# I2C_EEPROM_AT24C32.net
KiCad netlist of a schematic drawn in Altium Designer
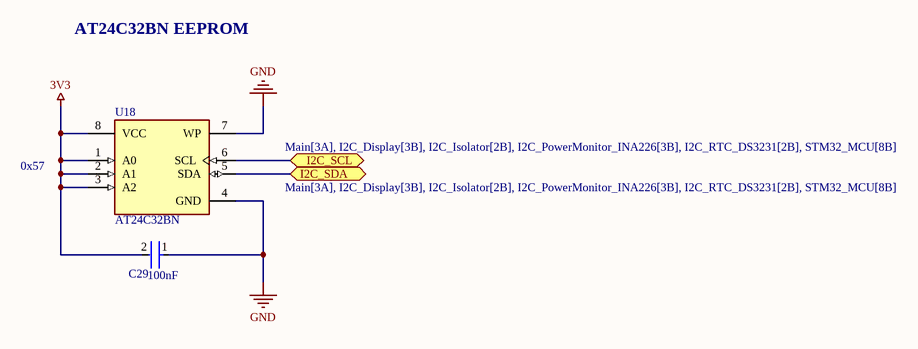
[diagram p0: I2C_EEPROM_AT24C32.SchDoc]

(export (version "E")
  (design (tool "Eeschema 10.0.6"))
  (components
    (comp (ref "C29")
      (value "100nF")
      (footprint "FP-CGA3E-0_3-0_1-IPC_A")
      (description "Cap Ceramic 100nF 50V X7R 10% Pad SMD 0603 +125°C Automotive T/R")
      (fields (field (name "TOLERANCE") "10%") (field (name "VOLTAGE") "50V"))
      (libsource (lib "Altium Content Vault") (part "b4654b650e69147ec39a6b967a45e02"))
    )
    (comp (ref "U18")
      (value "AT24C32BN")
      (footprint "FP-C04-057-SN-MFG")
      (description "IC EEPROM 32KBIT I2C 1MHZ 8SOIC")
      (libsource (lib "Altium Content Vault") (part "960d20628f40e82aadef76fa2b2e794"))
    )
  )
  (nets
    (net (code "1") (name "/I2C_SCL") (class "Default")
      (node (ref "U18") (pin "6") (pinfunction "SCL_6") (pintype "input"))
    )
    (net (code "2") (name "/I2C_SDA") (class "Default")
      (node (ref "U18") (pin "5") (pinfunction "SDA_5") (pintype "bidirectional"))
    )
    (net (code "3") (name "3V3") (class "Default")
      (node (ref "C29") (pin "2") (pinfunction "2_2") (pintype "passive"))
      (node (ref "U18") (pin "1") (pinfunction "A0_1") (pintype "input"))
      (node (ref "U18") (pin "2") (pinfunction "A1_2") (pintype "input"))
      (node (ref "U18") (pin "3") (pinfunction "A2_3") (pintype "input"))
      (node (ref "U18") (pin "8") (pinfunction "VCC_8") (pintype "power_in"))
    )
    (net (code "4") (name "GND") (class "Default")
      (node (ref "C29") (pin "1") (pinfunction "1_1") (pintype "passive"))
      (node (ref "U18") (pin "4") (pinfunction "GND_4") (pintype "power_in"))
      (node (ref "U18") (pin "7") (pinfunction "WP_7") (pintype "passive"))
    )
  )
)
